# SB2030_Logger_ESP32.net
KiCad netlist of a schematic drawn in EAGLE
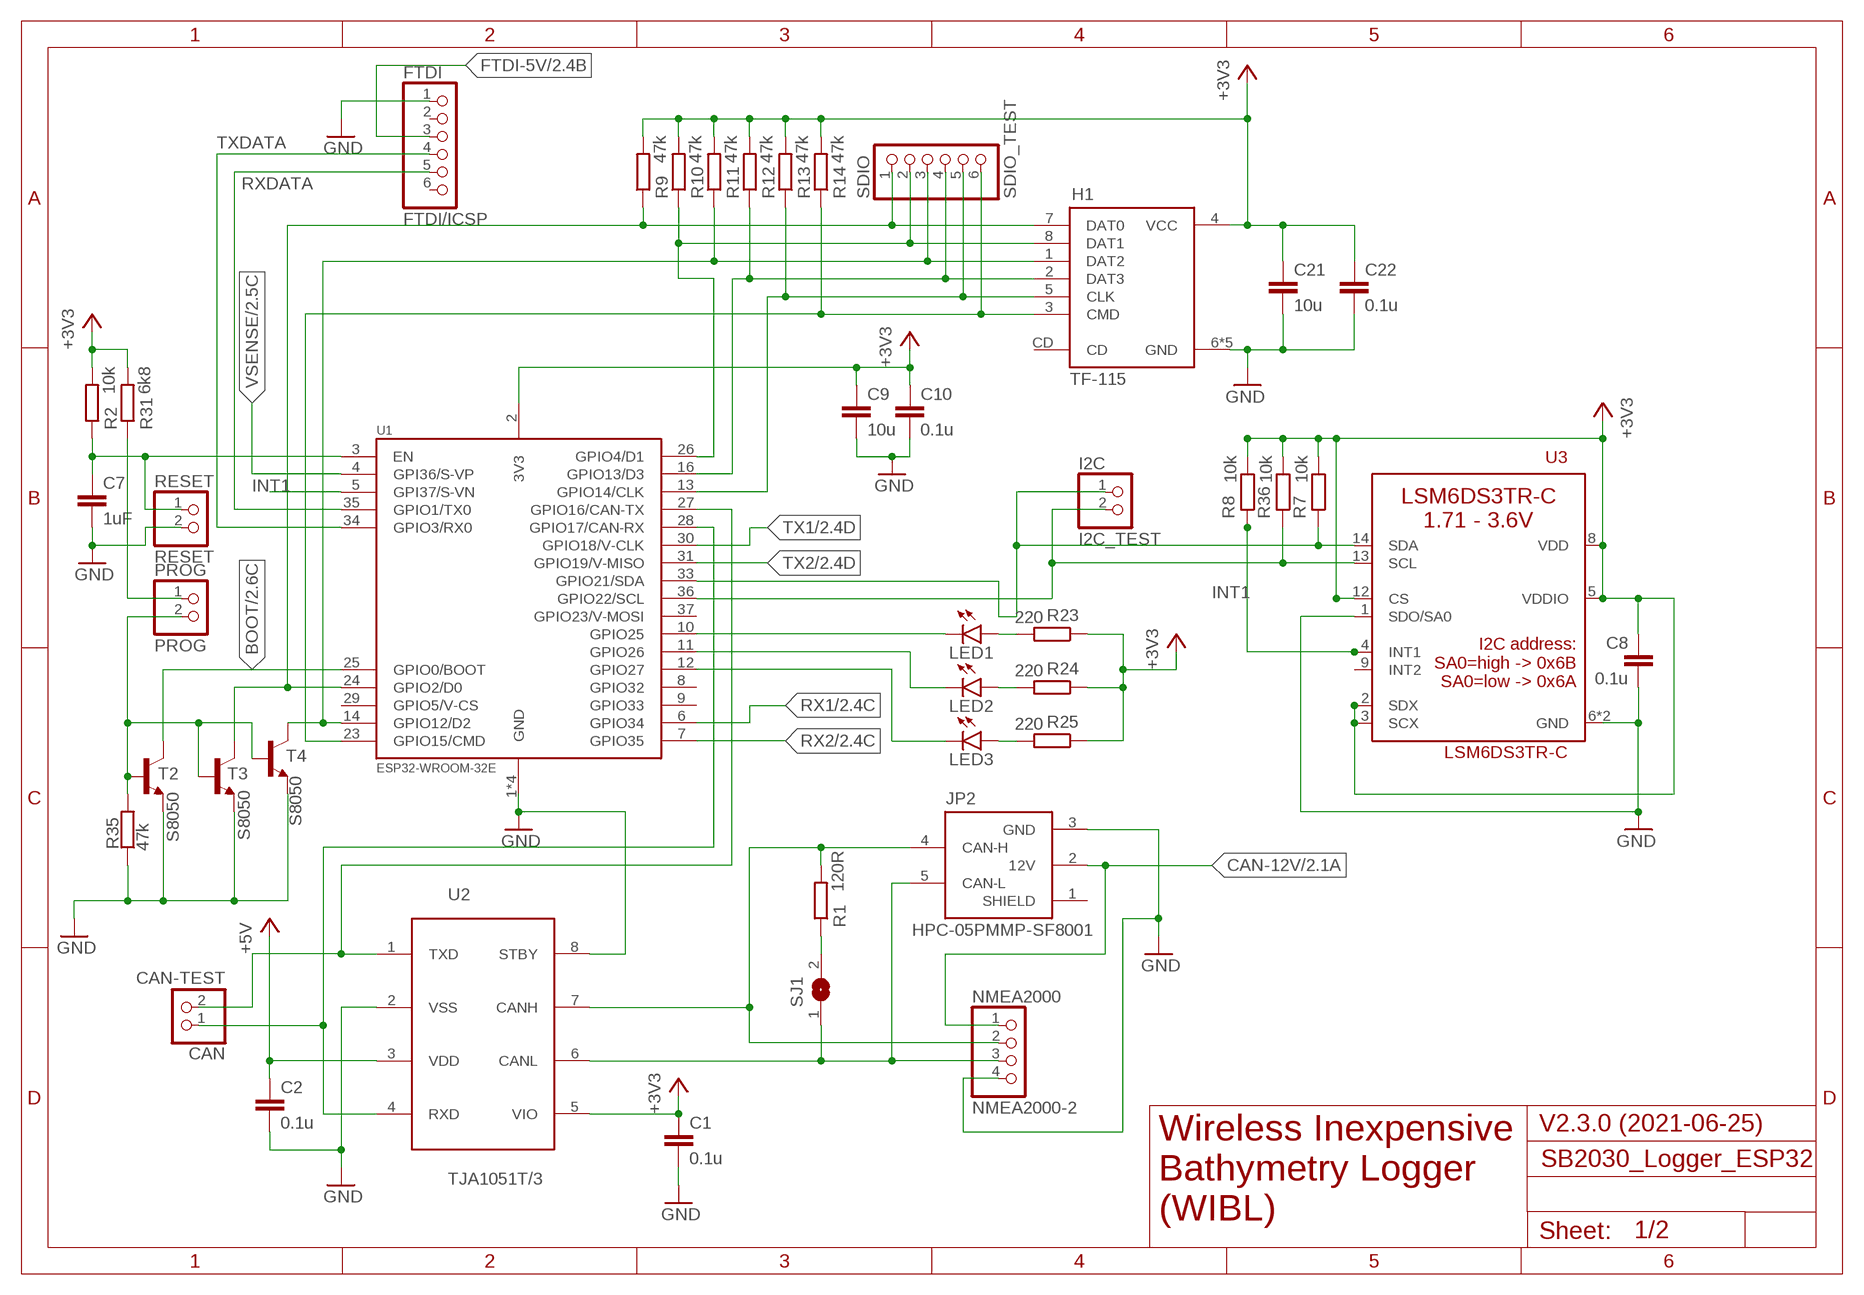
[diagram p0: schematic, sheet 1]
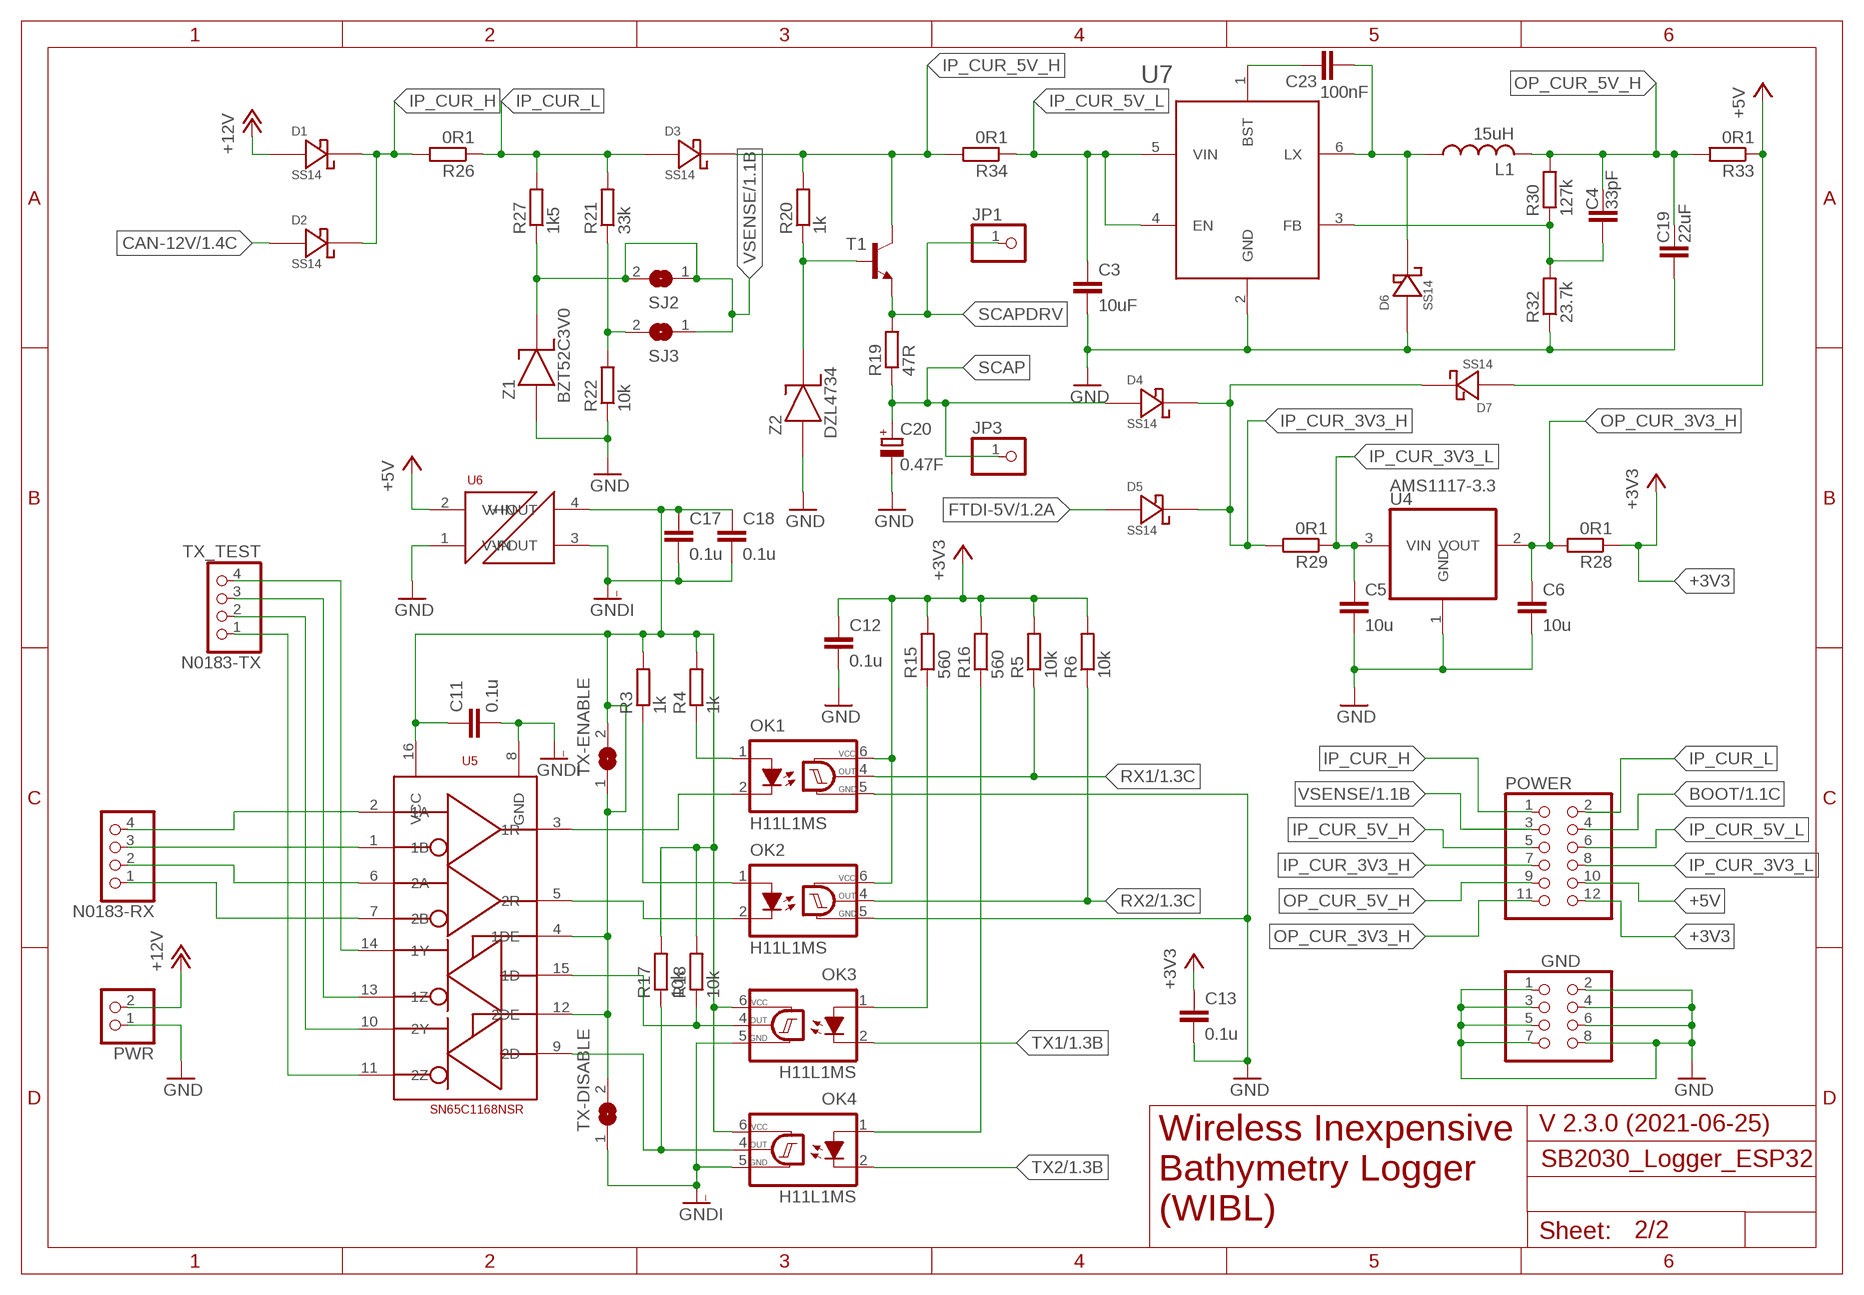
[diagram p1: schematic, sheet 2]

(export (version "E")
  (design (tool "Eeschema 10.0.6"))
  (components
    (comp (ref "C1")
      (value "0.1u")
      (footprint "eagle-import:C0805")
      (libsource (lib "eagle-import") (part "C-EUC0805"))
    )
    (comp (ref "C2")
      (value "0.1u")
      (footprint "eagle-import:C0805")
      (libsource (lib "eagle-import") (part "C-EUC0805"))
    )
    (comp (ref "C7")
      (value "1uF")
      (footprint "eagle-import:C0805")
      (libsource (lib "eagle-import") (part "C-EUC0805"))
    )
    (comp (ref "C8")
      (value "0.1u")
      (footprint "eagle-import:C0805")
      (libsource (lib "eagle-import") (part "C-EUC0805"))
    )
    (comp (ref "C9")
      (value "10u")
      (footprint "eagle-import:C0805")
      (libsource (lib "eagle-import") (part "C-EUC0805"))
    )
    (comp (ref "C10")
      (value "0.1u")
      (footprint "eagle-import:C0805")
      (libsource (lib "eagle-import") (part "C-EUC0805"))
    )
    (comp (ref "C21")
      (value "10u")
      (footprint "eagle-import:C0805")
      (libsource (lib "eagle-import") (part "C-EUC0805"))
    )
    (comp (ref "C22")
      (value "0.1u")
      (footprint "eagle-import:C0805")
      (libsource (lib "eagle-import") (part "C-EUC0805"))
    )
    (comp (ref "CAN")
      (value "CAN-TEST")
      (footprint "eagle-import:1X02")
      (libsource (lib "eagle-import") (part "PINHD-1X2"))
    )
    (comp (ref "FTDI")
      (value "FTDI/ICSP")
      (footprint "eagle-import:1X06")
      (libsource (lib "eagle-import") (part "PINHD-1X6"))
    )
    (comp (ref "H1")
      (value "TF-115")
      (footprint "eagle-import:XUNPU-MICROSD-SOCKET")
      (libsource (lib "eagle-import") (part "XUNPU-MICROSD-SOCKET"))
    )
    (comp (ref "I2C")
      (value "I2C_TEST")
      (footprint "eagle-import:1X02")
      (libsource (lib "eagle-import") (part "PINHD-1X2"))
    )
    (comp (ref "JP2")
      (value "HPC-05PMMP-SF8001")
      (footprint "eagle-import:NMEA2000")
      (libsource (lib "eagle-import") (part "NMEA2000"))
    )
    (comp (ref "LED1")
      (value "LEDCHIP-LED0603")
      (footprint "eagle-import:CHIP-LED0603")
      (libsource (lib "eagle-import") (part "LEDCHIP-LED0603"))
    )
    (comp (ref "LED2")
      (value "LEDCHIP-LED0603")
      (footprint "eagle-import:CHIP-LED0603")
      (libsource (lib "eagle-import") (part "LEDCHIP-LED0603"))
    )
    (comp (ref "LED3")
      (value "LEDCHIP-LED0603")
      (footprint "eagle-import:CHIP-LED0603")
      (libsource (lib "eagle-import") (part "LEDCHIP-LED0603"))
    )
    (comp (ref "NMEA2000")
      (value "NMEA2000-2")
      (footprint "eagle-import:1X04")
      (libsource (lib "eagle-import") (part "PINHD-1X4"))
    )
    (comp (ref "PROG")
      (value "PROG")
      (footprint "eagle-import:1X02")
      (libsource (lib "eagle-import") (part "PINHD-1X2"))
    )
    (comp (ref "R1")
      (value "120R")
      (footprint "eagle-import:R0805")
      (libsource (lib "eagle-import") (part "R-EU_R0805"))
    )
    (comp (ref "R2")
      (value "10k")
      (footprint "eagle-import:R0805")
      (libsource (lib "eagle-import") (part "R-EU_R0805"))
    )
    (comp (ref "R7")
      (value "10k")
      (footprint "eagle-import:R0805")
      (libsource (lib "eagle-import") (part "R-EU_R0805"))
    )
    (comp (ref "R8")
      (value "10k")
      (footprint "eagle-import:R0805")
      (libsource (lib "eagle-import") (part "R-EU_R0805"))
    )
    (comp (ref "R9")
      (value "47k")
      (footprint "eagle-import:R0805")
      (libsource (lib "eagle-import") (part "R-EU_R0805"))
    )
    (comp (ref "R10")
      (value "47k")
      (footprint "eagle-import:R0805")
      (libsource (lib "eagle-import") (part "R-EU_R0805"))
    )
    (comp (ref "R11")
      (value "47k")
      (footprint "eagle-import:R0805")
      (libsource (lib "eagle-import") (part "R-EU_R0805"))
    )
    (comp (ref "R12")
      (value "47k")
      (footprint "eagle-import:R0805")
      (libsource (lib "eagle-import") (part "R-EU_R0805"))
    )
    (comp (ref "R13")
      (value "47k")
      (footprint "eagle-import:R0805")
      (libsource (lib "eagle-import") (part "R-EU_R0805"))
    )
    (comp (ref "R14")
      (value "47k")
      (footprint "eagle-import:R0805")
      (libsource (lib "eagle-import") (part "R-EU_R0805"))
    )
    (comp (ref "R23")
      (value "220")
      (footprint "eagle-import:R0805")
      (libsource (lib "eagle-import") (part "R-EU_R0805"))
    )
    (comp (ref "R24")
      (value "220")
      (footprint "eagle-import:R0805")
      (libsource (lib "eagle-import") (part "R-EU_R0805"))
    )
    (comp (ref "R25")
      (value "220")
      (footprint "eagle-import:R0805")
      (libsource (lib "eagle-import") (part "R-EU_R0805"))
    )
    (comp (ref "R31")
      (value "6k8")
      (footprint "eagle-import:R0805")
      (libsource (lib "eagle-import") (part "R-EU_R0805"))
    )
    (comp (ref "R35")
      (value "47k")
      (footprint "eagle-import:R0805")
      (libsource (lib "eagle-import") (part "R-EU_R0805"))
    )
    (comp (ref "R36")
      (value "10k")
      (footprint "eagle-import:R0805")
      (libsource (lib "eagle-import") (part "R-EU_R0805"))
    )
    (comp (ref "RESET")
      (value "RESET")
      (footprint "eagle-import:1X02")
      (libsource (lib "eagle-import") (part "PINHD-1X2"))
    )
    (comp (ref "SDIO")
      (value "SDIO_TEST")
      (footprint "eagle-import:1X06")
      (libsource (lib "eagle-import") (part "PINHD-1X6"))
    )
    (comp (ref "SJ1") (value "SJ") (footprint "eagle-import:SJ") (libsource (lib "eagle-import") (part "SJ")))
    (comp (ref "T2")
      (value "S8050")
      (footprint "eagle-import:SOT23")
      (libsource (lib "eagle-import") (part "BC846"))
    )
    (comp (ref "T3")
      (value "S8050")
      (footprint "eagle-import:SOT23")
      (libsource (lib "eagle-import") (part "BC846"))
    )
    (comp (ref "T4")
      (value "S8050")
      (footprint "eagle-import:SOT23")
      (libsource (lib "eagle-import") (part "BC846"))
    )
    (comp (ref "U1")
      (value "ESP32-WROOM-32E")
      (footprint "eagle-import:ESPS32-WROOM-32E")
      (libsource (lib "eagle-import") (part "ESP32-WROOM-32E"))
    )
    (comp (ref "U2")
      (value "TJA1051T/3")
      (footprint "eagle-import:SOIC8")
      (libsource (lib "eagle-import") (part "MCP2562T-E/SN"))
    )
    (comp (ref "U3")
      (value "LSM6DS3TR-C")
      (footprint "eagle-import:LGA-14-2.5X3MM")
      (fields (field (name "MF") "STMicroelectronics"))
      (libsource (lib "eagle-import") (part "LSM6DS3TR-C"))
    )
    (comp (ref "C3")
      (value "10uF")
      (footprint "eagle-import:C1206")
      (libsource (lib "eagle-import") (part "C-EUC1206"))
    )
    (comp (ref "C4")
      (value "33pF")
      (footprint "eagle-import:C0603")
      (libsource (lib "eagle-import") (part "C-EUC0603"))
    )
    (comp (ref "C5")
      (value "10u")
      (footprint "eagle-import:C0805")
      (libsource (lib "eagle-import") (part "C-EUC0805"))
    )
    (comp (ref "C6")
      (value "10u")
      (footprint "eagle-import:C0805")
      (libsource (lib "eagle-import") (part "C-EUC0805"))
    )
    (comp (ref "C11")
      (value "0.1u")
      (footprint "eagle-import:C0805")
      (libsource (lib "eagle-import") (part "C-EUC0805"))
    )
    (comp (ref "C12")
      (value "0.1u")
      (footprint "eagle-import:C0805")
      (libsource (lib "eagle-import") (part "C-EUC0805"))
    )
    (comp (ref "C13")
      (value "0.1u")
      (footprint "eagle-import:C0805")
      (libsource (lib "eagle-import") (part "C-EUC0805"))
    )
    (comp (ref "C17")
      (value "0.1u")
      (footprint "eagle-import:C0805")
      (libsource (lib "eagle-import") (part "C-EUC0805"))
    )
    (comp (ref "C18")
      (value "0.1u")
      (footprint "eagle-import:C0805")
      (libsource (lib "eagle-import") (part "C-EUC0805"))
    )
    (comp (ref "C19")
      (value "22uF")
      (footprint "eagle-import:C0603")
      (libsource (lib "eagle-import") (part "C-EUC0603"))
    )
    (comp (ref "C20")
      (value "0.47F")
      (footprint "eagle-import:P128-50")
      (libsource (lib "eagle-import") (part "CPOL-EUP128-50"))
    )
    (comp (ref "C23")
      (value "100nF")
      (footprint "eagle-import:C0402")
      (libsource (lib "eagle-import") (part "C0402"))
    )
    (comp (ref "D1")
      (value "SS14")
      (footprint "eagle-import:DO-214AC")
      (libsource (lib "eagle-import") (part "SS14"))
    )
    (comp (ref "D2")
      (value "SS14")
      (footprint "eagle-import:DO-214AC")
      (libsource (lib "eagle-import") (part "SS14"))
    )
    (comp (ref "D3")
      (value "SS14")
      (footprint "eagle-import:DO-214AC")
      (libsource (lib "eagle-import") (part "SS14"))
    )
    (comp (ref "D4")
      (value "SS14")
      (footprint "eagle-import:DO-214AC")
      (libsource (lib "eagle-import") (part "SS14"))
    )
    (comp (ref "D5")
      (value "SS14")
      (footprint "eagle-import:DO-214AC")
      (libsource (lib "eagle-import") (part "SS14"))
    )
    (comp (ref "D6")
      (value "SS14")
      (footprint "eagle-import:DO-214AC")
      (libsource (lib "eagle-import") (part "SS14"))
    )
    (comp (ref "D7")
      (value "SS14")
      (footprint "eagle-import:DO-214AC")
      (libsource (lib "eagle-import") (part "SS14"))
    )
    (comp (ref "GND")
      (value "PINHD-2X4")
      (footprint "eagle-import:2X04")
      (libsource (lib "eagle-import") (part "PINHD-2X4"))
    )
    (comp (ref "JP1")
      (value "PINHD-1X1")
      (footprint "eagle-import:1X01")
      (libsource (lib "eagle-import") (part "PINHD-1X1"))
    )
    (comp (ref "JP3")
      (value "PINHD-1X1")
      (footprint "eagle-import:1X01")
      (libsource (lib "eagle-import") (part "PINHD-1X1"))
    )
    (comp (ref "L1")
      (value "15uH")
      (footprint "eagle-import:MWSA0603S")
      (libsource (lib "eagle-import") (part "MWSA0603S"))
    )
    (comp (ref "N0183-RX")
      (value "PINHD-1X4")
      (footprint "eagle-import:1X04")
      (libsource (lib "eagle-import") (part "PINHD-1X4"))
    )
    (comp (ref "N0183-TX")
      (value "TX_TEST")
      (footprint "eagle-import:1X04")
      (libsource (lib "eagle-import") (part "PINHD-1X4"))
    )
    (comp (ref "OK1")
      (value "H11L1MS")
      (footprint "eagle-import:DIL6-SMD")
      (libsource (lib "eagle-import") (part "H11LMS1"))
    )
    (comp (ref "OK2")
      (value "H11L1MS")
      (footprint "eagle-import:DIL6-SMD")
      (libsource (lib "eagle-import") (part "H11LMS1"))
    )
    (comp (ref "OK3")
      (value "H11L1MS")
      (footprint "eagle-import:DIL6-SMD")
      (libsource (lib "eagle-import") (part "H11LMS1"))
    )
    (comp (ref "OK4")
      (value "H11L1MS")
      (footprint "eagle-import:DIL6-SMD")
      (libsource (lib "eagle-import") (part "H11LMS1"))
    )
    (comp (ref "POWER")
      (value "PINHD-2X6")
      (footprint "eagle-import:2X06")
      (libsource (lib "eagle-import") (part "PINHD-2X6"))
    )
    (comp (ref "PWR")
      (value "PINHD-1X2")
      (footprint "eagle-import:1X02")
      (libsource (lib "eagle-import") (part "PINHD-1X2"))
    )
    (comp (ref "R3")
      (value "1k")
      (footprint "eagle-import:R0805")
      (libsource (lib "eagle-import") (part "R-EU_R0805"))
    )
    (comp (ref "R4")
      (value "1k")
      (footprint "eagle-import:R0805")
      (libsource (lib "eagle-import") (part "R-EU_R0805"))
    )
    (comp (ref "R5")
      (value "10k")
      (footprint "eagle-import:R0805")
      (libsource (lib "eagle-import") (part "R-EU_R0805"))
    )
    (comp (ref "R6")
      (value "10k")
      (footprint "eagle-import:R0805")
      (libsource (lib "eagle-import") (part "R-EU_R0805"))
    )
    (comp (ref "R15")
      (value "560")
      (footprint "eagle-import:R0805")
      (libsource (lib "eagle-import") (part "R-EU_R0805"))
    )
    (comp (ref "R16")
      (value "560")
      (footprint "eagle-import:R0805")
      (libsource (lib "eagle-import") (part "R-EU_R0805"))
    )
    (comp (ref "R17")
      (value "10k")
      (footprint "eagle-import:R0805")
      (libsource (lib "eagle-import") (part "R-EU_R0805"))
    )
    (comp (ref "R18")
      (value "10k")
      (footprint "eagle-import:R0805")
      (libsource (lib "eagle-import") (part "R-EU_R0805"))
    )
    (comp (ref "R19")
      (value "47R")
      (footprint "eagle-import:R0805")
      (libsource (lib "eagle-import") (part "R-EU_R0805"))
    )
    (comp (ref "R20")
      (value "1k")
      (footprint "eagle-import:R0805")
      (libsource (lib "eagle-import") (part "R-EU_R0805"))
    )
    (comp (ref "R21")
      (value "33k")
      (footprint "eagle-import:R0805")
      (libsource (lib "eagle-import") (part "R-EU_R0805"))
    )
    (comp (ref "R22")
      (value "10k")
      (footprint "eagle-import:R0805")
      (libsource (lib "eagle-import") (part "R-EU_R0805"))
    )
    (comp (ref "R26")
      (value "0R1")
      (footprint "eagle-import:R0603")
      (libsource (lib "eagle-import") (part "R-EU_R0603"))
    )
    (comp (ref "R27")
      (value "1k5")
      (footprint "eagle-import:R0805")
      (libsource (lib "eagle-import") (part "R-EU_R0805"))
    )
    (comp (ref "R28")
      (value "0R1")
      (footprint "eagle-import:R0603")
      (libsource (lib "eagle-import") (part "R-EU_R0603"))
    )
    (comp (ref "R29")
      (value "0R1")
      (footprint "eagle-import:R0603")
      (libsource (lib "eagle-import") (part "R-EU_R0603"))
    )
    (comp (ref "R30")
      (value "127k")
      (footprint "eagle-import:R0603")
      (libsource (lib "eagle-import") (part "R-EU_R0603"))
    )
    (comp (ref "R32")
      (value "23.7k")
      (footprint "eagle-import:R0603")
      (libsource (lib "eagle-import") (part "R-EU_R0603"))
    )
    (comp (ref "R33")
      (value "0R1")
      (footprint "eagle-import:R0603")
      (libsource (lib "eagle-import") (part "R-EU_R0603"))
    )
    (comp (ref "R34")
      (value "0R1")
      (footprint "eagle-import:R0603")
      (libsource (lib "eagle-import") (part "R-EU_R0603"))
    )
    (comp (ref "SJ2") (value "SJ") (footprint "eagle-import:SJ") (libsource (lib "eagle-import") (part "SJ")))
    (comp (ref "SJ3") (value "SJ") (footprint "eagle-import:SJ") (libsource (lib "eagle-import") (part "SJ")))
    (comp (ref "T1")
      (value "BC817-16-NPN-SOT23-BEC")
      (footprint "eagle-import:SOT23-BEC")
      (libsource (lib "eagle-import") (part "-NPN-SOT23-BECBC817-16"))
    )
    (comp (ref "TX-DISABLE")
      (value "SJ")
      (footprint "eagle-import:SJ")
      (libsource (lib "eagle-import") (part "SJ"))
    )
    (comp (ref "TX-ENABLE")
      (value "SJ")
      (footprint "eagle-import:SJ")
      (libsource (lib "eagle-import") (part "SJ"))
    )
    (comp (ref "U4")
      (value "AMS1117-3.3")
      (footprint "eagle-import:SOT223")
      (fields (field (name "MPN") "REG1117"))
      (libsource (lib "eagle-import") (part "REG1117"))
    )
    (comp (ref "U5")
      (value "SN65C1168NSR")
      (footprint "eagle-import:SOIC16")
      (libsource (lib "eagle-import") (part "SN65C1168-SOIC"))
    )
    (comp (ref "U6")
      (value "RFM-0505S")
      (footprint "eagle-import:RFM-0505S")
      (libsource (lib "eagle-import") (part "RFM-0505S"))
    )
    (comp (ref "U7")
      (value "BL9352A")
      (footprint "eagle-import:SOT-23-6L")
      (libsource (lib "eagle-import") (part "BL9352A"))
    )
    (comp (ref "Z1")
      (value "BZT52C3V0")
      (footprint "eagle-import:SOD123")
      (libsource (lib "eagle-import") (part "BZT52C3V0"))
    )
    (comp (ref "Z2")
      (value "DZL4734")
      (footprint "eagle-import:SOD-123FL")
      (libsource (lib "eagle-import") (part "DZL4734"))
    )
  )
  (nets
    (net (code "1") (name "+3V3") (class "Default")
      (node (ref "C1") (pin "1") (pinfunction "1_1") (pintype "passive"))
      (node (ref "C10") (pin "1") (pinfunction "1_1") (pintype "passive"))
      (node (ref "C12") (pin "1") (pinfunction "1_1") (pintype "passive"))
      (node (ref "C13") (pin "1") (pinfunction "1_1") (pintype "passive"))
      (node (ref "C21") (pin "1") (pinfunction "1_1") (pintype "passive"))
      (node (ref "C22") (pin "1") (pinfunction "1_1") (pintype "passive"))
      (node (ref "C8") (pin "1") (pinfunction "1_1") (pintype "passive"))
      (node (ref "C9") (pin "1") (pinfunction "1_1") (pintype "passive"))
      (node (ref "H1") (pin "4") (pinfunction "VCC_4") (pintype "bidirectional"))
      (node (ref "OK1") (pin "6") (pinfunction "VCC_6") (pintype "power_in"))
      (node (ref "OK2") (pin "6") (pinfunction "VCC_6") (pintype "power_in"))
      (node (ref "POWER") (pin "12") (pinfunction "12_12") (pintype "passive"))
      (node (ref "R10") (pin "2") (pinfunction "2_2") (pintype "passive"))
      (node (ref "R11") (pin "2") (pinfunction "2_2") (pintype "passive"))
      (node (ref "R12") (pin "2") (pinfunction "2_2") (pintype "passive"))
      (node (ref "R13") (pin "2") (pinfunction "2_2") (pintype "passive"))
      (node (ref "R14") (pin "2") (pinfunction "2_2") (pintype "passive"))
      (node (ref "R15") (pin "2") (pinfunction "2_2") (pintype "passive"))
      (node (ref "R16") (pin "2") (pinfunction "2_2") (pintype "passive"))
      (node (ref "R2") (pin "2") (pinfunction "2_2") (pintype "passive"))
      (node (ref "R23") (pin "1") (pinfunction "1_1") (pintype "passive"))
      (node (ref "R24") (pin "1") (pinfunction "1_1") (pintype "passive"))
      (node (ref "R25") (pin "1") (pinfunction "1_1") (pintype "passive"))
      (node (ref "R28") (pin "1") (pinfunction "1_1") (pintype "passive"))
      (node (ref "R31") (pin "2") (pinfunction "2_2") (pintype "passive"))
      (node (ref "R36") (pin "2") (pinfunction "2_2") (pintype "passive"))
      (node (ref "R5") (pin "2") (pinfunction "2_2") (pintype "passive"))
      (node (ref "R6") (pin "2") (pinfunction "2_2") (pintype "passive"))
      (node (ref "R7") (pin "2") (pinfunction "2_2") (pintype "passive"))
      (node (ref "R8") (pin "2") (pinfunction "2_2") (pintype "passive"))
      (node (ref "R9") (pin "2") (pinfunction "2_2") (pintype "passive"))
      (node (ref "U1") (pin "2") (pinfunction "3V3_2") (pintype "bidirectional"))
      (node (ref "U2") (pin "5") (pinfunction "VIO_5") (pintype "bidirectional"))
      (node (ref "U3") (pin "12") (pinfunction "CS_12") (pintype "bidirectional"))
      (node (ref "U3") (pin "2") (pinfunction "SDX_2") (pintype "bidirectional"))
      (node (ref "U3") (pin "3") (pinfunction "SCX_3") (pintype "bidirectional"))
      (node (ref "U3") (pin "5") (pinfunction "VDDIO_5") (pintype "bidirectional"))
      (node (ref "U3") (pin "8") (pinfunction "VDD_8") (pintype "bidirectional"))
    )
    (net (code "2") (name "+5V") (class "Default")
      (node (ref "C2") (pin "1") (pinfunction "1_1") (pintype "passive"))
      (node (ref "D7") (pin "A") (pinfunction "A_A") (pintype "bidirectional"))
      (node (ref "POWER") (pin "10") (pinfunction "10_10") (pintype "passive"))
      (node (ref "R33") (pin "1") (pinfunction "1_1") (pintype "passive"))
      (node (ref "U2") (pin "3") (pinfunction "VDD_3") (pintype "bidirectional"))
      (node (ref "U6") (pin "2") (pinfunction "V+IN_2") (pintype "bidirectional"))
    )
    (net (code "3") (name "+12V") (class "Default")
      (node (ref "D1") (pin "A") (pinfunction "A_A") (pintype "bidirectional"))
      (node (ref "PWR") (pin "2") (pinfunction "2_2") (pintype "passive"))
    )
    (net (code "4") (name "BOOT") (class "Default")
      (node (ref "POWER") (pin "4") (pinfunction "4_4") (pintype "passive"))
      (node (ref "T2") (pin "3") (pinfunction "C_3") (pintype "passive"))
      (node (ref "U1") (pin "25") (pinfunction "GPIO0/BOOT_25") (pintype "bidirectional"))
    )
    (net (code "5") (name "CAN-12V") (class "Default")
      (node (ref "D2") (pin "A") (pinfunction "A_A") (pintype "bidirectional"))
      (node (ref "JP2") (pin "2") (pinfunction "12V_2") (pintype "bidirectional"))
      (node (ref "NMEA2000") (pin "1") (pinfunction "1_1") (pintype "passive"))
    )
    (net (code "6") (name "FTDI-5V") (class "Default")
      (node (ref "D5") (pin "A") (pinfunction "A_A") (pintype "bidirectional"))
      (node (ref "FTDI") (pin "3") (pinfunction "3_3") (pintype "passive"))
    )
    (net (code "7") (name "GND") (class "Default")
      (node (ref "C1") (pin "2") (pinfunction "2_2") (pintype "passive"))
      (node (ref "C10") (pin "2") (pinfunction "2_2") (pintype "passive"))
      (node (ref "C12") (pin "2") (pinfunction "2_2") (pintype "passive"))
      (node (ref "C13") (pin "2") (pinfunction "2_2") (pintype "passive"))
      (node (ref "C19") (pin "1") (pinfunction "1_1") (pintype "passive"))
      (node (ref "C2") (pin "2") (pinfunction "2_2") (pintype "passive"))
      (node (ref "C20") (pin "-") (pinfunction "-_-") (pintype "passive"))
      (node (ref "C21") (pin "2") (pinfunction "2_2") (pintype "passive"))
      (node (ref "C22") (pin "2") (pinfunction "2_2") (pintype "passive"))
      (node (ref "C3") (pin "2") (pinfunction "2_2") (pintype "passive"))
      (node (ref "C5") (pin "2") (pinfunction "2_2") (pintype "passive"))
      (node (ref "C6") (pin "2") (pinfunction "2_2") (pintype "passive"))
      (node (ref "C7") (pin "2") (pinfunction "2_2") (pintype "passive"))
      (node (ref "C8") (pin "2") (pinfunction "2_2") (pintype "passive"))
      (node (ref "C9") (pin "2") (pinfunction "2_2") (pintype "passive"))
      (node (ref "D6") (pin "A") (pinfunction "A_A") (pintype "bidirectional"))
      (node (ref "FTDI") (pin "1") (pinfunction "1_1") (pintype "passive"))
      (node (ref "GND") (pin "1") (pinfunction "1_1") (pintype "passive"))
      (node (ref "GND") (pin "2") (pinfunction "2_2") (pintype "passive"))
      (node (ref "GND") (pin "3") (pinfunction "3_3") (pintype "passive"))
      (node (ref "GND") (pin "4") (pinfunction "4_4") (pintype "passive"))
      (node (ref "GND") (pin "5") (pinfunction "5_5") (pintype "passive"))
      (node (ref "GND") (pin "6") (pinfunction "6_6") (pintype "passive"))
      (node (ref "GND") (pin "7") (pinfunction "7_7") (pintype "passive"))
      (node (ref "GND") (pin "8") (pinfunction "8_8") (pintype "passive"))
      (node (ref "H1") (pin "6") (pinfunction "GND_6") (pintype "bidirectional"))
      (node (ref "H1") (pin "GND1") (pinfunction "GND_GND1") (pintype "bidirectional"))
      (node (ref "H1") (pin "GND2") (pinfunction "GND_GND2") (pintype "bidirectional"))
      (node (ref "H1") (pin "GND3") (pinfunction "GND_GND3") (pintype "bidirectional"))
      (node (ref "H1") (pin "GND4") (pinfunction "GND_GND4") (pintype "bidirectional"))
      (node (ref "JP2") (pin "3") (pinfunction "GND_3") (pintype "bidirectional"))
      (node (ref "NMEA2000") (pin "4") (pinfunction "4_4") (pintype "passive"))
      (node (ref "OK1") (pin "5") (pinfunction "GND_5") (pintype "power_in"))
      (node (ref "OK2") (pin "5") (pinfunction "GND_5") (pintype "power_in"))
      (node (ref "PWR") (pin "1") (pinfunction "1_1") (pintype "passive"))
      (node (ref "R22") (pin "1") (pinfunction "1_1") (pintype "passive"))
      (node (ref "R32") (pin "1") (pinfunction "1_1") (pintype "passive"))
      (node (ref "R35") (pin "1") (pinfunction "1_1") (pintype "passive"))
      (node (ref "RESET") (pin "2") (pinfunction "2_2") (pintype "passive"))
      (node (ref "T2") (pin "2") (pinfunction "E_2") (pintype "passive"))
      (node (ref "T3") (pin "2") (pinfunction "E_2") (pintype "passive"))
      (node (ref "T4") (pin "2") (pinfunction "E_2") (pintype "passive"))
      (node (ref "U1") (pin "1") (pinfunction "GND_1") (pintype "bidirectional"))
      (node (ref "U1") (pin "15") (pinfunction "GND_15") (pintype "bidirectional"))
      (node (ref "U1") (pin "38") (pinfunction "GND_38") (pintype "bidirectional"))
      (node (ref "U1") (pin "THERM") (pinfunction "GND_THERM") (pintype "bidirectional"))
      (node (ref "U2") (pin "2") (pinfunction "VSS_2") (pintype "bidirectional"))
      (node (ref "U2") (pin "8") (pinfunction "STBY_8") (pintype "bidirectional"))
      (node (ref "U3") (pin "1") (pinfunction "SDO/SA0_1") (pintype "bidirectional"))
      (node (ref "U3") (pin "6") (pinfunction "GND_6") (pintype "bidirectional"))
      (node (ref "U3") (pin "7") (pinfunction "GND_7") (pintype "bidirectional"))
      (node (ref "U4") (pin "1") (pinfunction "GND_1") (pintype "power_in"))
      (node (ref "U6") (pin "1") (pinfunction "V-IN_1") (pintype "bidirectional"))
      (node (ref "U7") (pin "2") (pinfunction "GND_2") (pintype "bidirectional"))
      (node (ref "Z1") (pin "1") (pinfunction "A_1") (pintype "bidirectional"))
      (node (ref "Z2") (pin "A") (pinfunction "A_A") (pintype "bidirectional"))
    )
    (net (code "8") (name "GNDI") (class "Default")
      (node (ref "C11") (pin "2") (pinfunction "2_2") (pintype "passive"))
      (node (ref "C17") (pin "2") (pinfunction "2_2") (pintype "passive"))
      (node (ref "C18") (pin "2") (pinfunction "2_2") (pintype "passive"))
      (node (ref "OK3") (pin "5") (pinfunction "GND_5") (pintype "power_in"))
      (node (ref "OK4") (pin "5") (pinfunction "GND_5") (pintype "power_in"))
      (node (ref "TX-DISABLE") (pin "1") (pinfunction "1_1") (pintype "passive"))
      (node (ref "U5") (pin "8") (pinfunction "GND_8") (pintype "bidirectional"))
      (node (ref "U6") (pin "3") (pinfunction "V-OUT_3") (pintype "bidirectional"))
    )
    (net (code "9") (name "INT1") (class "Default")
      (node (ref "R8") (pin "1") (pinfunction "1_1") (pintype "passive"))
      (node (ref "U1") (pin "5") (pinfunction "GPI37/S-VN_5") (pintype "bidirectional"))
      (node (ref "U3") (pin "4") (pinfunction "INT1_4") (pintype "bidirectional"))
    )
    (net (code "10") (name "IP_CUR_3V3_H") (class "Default")
      (node (ref "D4") (pin "K") (pinfunction "K_K") (pintype "bidirectional"))
      (node (ref "D5") (pin "K") (pinfunction "K_K") (pintype "bidirectional"))
      (node (ref "D7") (pin "K") (pinfunction "K_K") (pintype "bidirectional"))
      (node (ref "POWER") (pin "7") (pinfunction "7_7") (pintype "passive"))
      (node (ref "R29") (pin "2") (pinfunction "2_2") (pintype "passive"))
    )
    (net (code "11") (name "IP_CUR_3V3_L") (class "Default")
      (node (ref "C5") (pin "1") (pinfunction "1_1") (pintype "passive"))
      (node (ref "POWER") (pin "8") (pinfunction "8_8") (pintype "passive"))
      (node (ref "R29") (pin "1") (pinfunction "1_1") (pintype "passive"))
      (node (ref "U4") (pin "3") (pinfunction "VIN_3") (pintype "input"))
    )
    (net (code "12") (name "IP_CUR_5V_H") (class "Default")
      (node (ref "D3") (pin "K") (pinfunction "K_K") (pintype "bidirectional"))
      (node (ref "POWER") (pin "5") (pinfunction "5_5") (pintype "passive"))
      (node (ref "R20") (pin "2") (pinfunction "2_2") (pintype "passive"))
      (node (ref "R34") (pin "2") (pinfunction "2_2") (pintype "passive"))
      (node (ref "T1") (pin "C") (pinfunction "C_C") (pintype "passive"))
    )
    (net (code "13") (name "IP_CUR_5V_L") (class "Default")
      (node (ref "C3") (pin "1") (pinfunction "1_1") (pintype "passive"))
      (node (ref "POWER") (pin "6") (pinfunction "6_6") (pintype "passive"))
      (node (ref "R34") (pin "1") (pinfunction "1_1") (pintype "passive"))
      (node (ref "U7") (pin "4") (pinfunction "EN_4") (pintype "bidirectional"))
      (node (ref "U7") (pin "5") (pinfunction "VIN_5") (pintype "bidirectional"))
    )
    (net (code "14") (name "IP_CUR_H") (class "Default")
      (node (ref "D1") (pin "K") (pinfunction "K_K") (pintype "bidirectional"))
      (node (ref "D2") (pin "K") (pinfunction "K_K") (pintype "bidirectional"))
      (node (ref "POWER") (pin "1") (pinfunction "1_1") (pintype "passive"))
      (node (ref "R26") (pin "2") (pinfunction "2_2") (pintype "passive"))
    )
    (net (code "15") (name "IP_CUR_L") (class "Default")
      (node (ref "D3") (pin "A") (pinfunction "A_A") (pintype "bidirectional"))
      (node (ref "POWER") (pin "2") (pinfunction "2_2") (pintype "passive"))
      (node (ref "R21") (pin "2") (pinfunction "2_2") (pintype "passive"))
      (node (ref "R26") (pin "1") (pinfunction "1_1") (pintype "passive"))
      (node (ref "R27") (pin "2") (pinfunction "2_2") (pintype "passive"))
    )
    (net (code "16") (name "Net-(C23-1)") (class "Default")
      (node (ref "C23") (pin "P$1") (pinfunction "1_P$1") (pintype "passive"))
      (node (ref "U7") (pin "1") (pinfunction "BST_1") (pintype "bidirectional"))
    )
    (net (code "17") (name "Net-(C23-2)") (class "Default")
      (node (ref "C23") (pin "P$2") (pinfunction "2_P$2") (pintype "passive"))
      (node (ref "D6") (pin "K") (pinfunction "K_K") (pintype "bidirectional"))
      (node (ref "L1") (pin "P$1") (pinfunction "1_P$1") (pintype "passive"))
      (node (ref "U7") (pin "6") (pinfunction "LX_6") (pintype "bidirectional"))
    )
    (net (code "18") (name "Net-(H1-CLK)") (class "Default")
      (node (ref "H1") (pin "5") (pinfunction "CLK_5") (pintype "bidirectional"))
      (node (ref "R13") (pin "1") (pinfunction "1_1") (pintype "passive"))
      (node (ref "SDIO") (pin "5") (pinfunction "5_5") (pintype "passive"))
      (node (ref "U1") (pin "13") (pinfunction "GPIO14/CLK_13") (pintype "bidirectional"))
    )
    (net (code "19") (name "Net-(H1-CMD)") (class "Default")
      (node (ref "H1") (pin "3") (pinfunction "CMD_3") (pintype "bidirectional"))
      (node (ref "R14") (pin "1") (pinfunction "1_1") (pintype "passive"))
      (node (ref "SDIO") (pin "6") (pinfunction "6_6") (pintype "passive"))
      (node (ref "U1") (pin "23") (pinfunction "GPIO15/CMD_23") (pintype "bidirectional"))
    )
    (net (code "20") (name "Net-(H1-DAT0)") (class "Default")
      (node (ref "H1") (pin "7") (pinfunction "DAT0_7") (pintype "bidirectional"))
      (node (ref "R9") (pin "1") (pinfunction "1_1") (pintype "passive"))
      (node (ref "SDIO") (pin "1") (pinfunction "1_1") (pintype "passive"))
      (node (ref "T3") (pin "3") (pinfunction "C_3") (pintype "passive"))
      (node (ref "U1") (pin "24") (pinfunction "GPIO2/D0_24") (pintype "bidirectional"))
    )
    (net (code "21") (name "Net-(H1-DAT1)") (class "Default")
      (node (ref "H1") (pin "8") (pinfunction "DAT1_8") (pintype "bidirectional"))
      (node (ref "R10") (pin "1") (pinfunction "1_1") (pintype "passive"))
      (node (ref "SDIO") (pin "2") (pinfunction "2_2") (pintype "passive"))
      (node (ref "U1") (pin "26") (pinfunction "GPIO4/D1_26") (pintype "bidirectional"))
    )
    (net (code "22") (name "Net-(H1-DAT2)") (class "Default")
      (node (ref "H1") (pin "1") (pinfunction "DAT2_1") (pintype "bidirectional"))
      (node (ref "R11") (pin "1") (pinfunction "1_1") (pintype "passive"))
      (node (ref "SDIO") (pin "3") (pinfunction "3_3") (pintype "passive"))
      (node (ref "T4") (pin "3") (pinfunction "C_3") (pintype "passive"))
      (node (ref "U1") (pin "14") (pinfunction "GPIO12/D2_14") (pintype "bidirectional"))
    )
    (net (code "23") (name "Net-(H1-DAT3)") (class "Default")
      (node (ref "H1") (pin "2") (pinfunction "DAT3_2") (pintype "bidirectional"))
      (node (ref "R12") (pin "1") (pinfunction "1_1") (pintype "passive"))
      (node (ref "SDIO") (pin "4") (pinfunction "4_4") (pintype "passive"))
      (node (ref "U1") (pin "16") (pinfunction "GPIO13/D3_16") (pintype "bidirectional"))
    )
    (net (code "24") (name "Net-(JP2-CAN-H)") (class "Default")
      (node (ref "JP2") (pin "4") (pinfunction "CAN-H_4") (pintype "bidirectional"))
      (node (ref "NMEA2000") (pin "2") (pinfunction "2_2") (pintype "passive"))
      (node (ref "R1") (pin "2") (pinfunction "2_2") (pintype "passive"))
      (node (ref "U2") (pin "7") (pinfunction "CANH_7") (pintype "bidirectional"))
    )
    (net (code "25") (name "Net-(JP2-CAN-L)") (class "Default")
      (node (ref "JP2") (pin "5") (pinfunction "CAN-L_5") (pintype "bidirectional"))
      (node (ref "NMEA2000") (pin "3") (pinfunction "3_3") (pintype "passive"))
      (node (ref "SJ1") (pin "1") (pinfunction "1_1") (pintype "passive"))
      (node (ref "U2") (pin "6") (pinfunction "CANL_6") (pintype "bidirectional"))
    )
    (net (code "26") (name "Net-(LED1-PadA)") (class "Default")
      (node (ref "LED1") (pin "A") (pinfunction "A_A") (pintype "passive"))
      (node (ref "R23") (pin "2") (pinfunction "2_2") (pintype "passive"))
    )
    (net (code "27") (name "Net-(LED2-PadA)") (class "Default")
      (node (ref "LED2") (pin "A") (pinfunction "A_A") (pintype "passive"))
      (node (ref "R24") (pin "2") (pinfunction "2_2") (pintype "passive"))
    )
    (net (code "28") (name "Net-(LED3-PadA)") (class "Default")
      (node (ref "LED3") (pin "A") (pinfunction "A_A") (pintype "passive"))
      (node (ref "R25") (pin "2") (pinfunction "2_2") (pintype "passive"))
    )
    (net (code "29") (name "Net-(OK1-A)") (class "Default")
      (node (ref "OK1") (pin "1") (pinfunction "A_1") (pintype "passive"))
      (node (ref "R4") (pin "1") (pinfunction "1_1") (pintype "passive"))
    )
    (net (code "30") (name "Net-(OK1-C)") (class "Default")
      (node (ref "OK1") (pin "2") (pinfunction "C_2") (pintype "passive"))
      (node (ref "U5") (pin "3") (pinfunction "1R_3") (pintype "bidirectional"))
    )
    (net (code "31") (name "Net-(OK2-A)") (class "Default")
      (node (ref "OK2") (pin "1") (pinfunction "A_1") (pintype "passive"))
      (node (ref "R3") (pin "1") (pinfunction "1_1") (pintype "passive"))
    )
    (net (code "32") (name "Net-(OK2-C)") (class "Default")
      (node (ref "OK2") (pin "2") (pinfunction "C_2") (pintype "passive"))
      (node (ref "U5") (pin "5") (pinfunction "2R_5") (pintype "bidirectional"))
    )
    (net (code "33") (name "Net-(OK3-A)") (class "Default")
      (node (ref "OK3") (pin "1") (pinfunction "A_1") (pintype "passive"))
      (node (ref "R15") (pin "1") (pinfunction "1_1") (pintype "passive"))
    )
    (net (code "34") (name "Net-(OK3-OUT)") (class "Default")
      (node (ref "OK3") (pin "4") (pinfunction "OUT_4") (pintype "output"))
      (node (ref "R18") (pin "1") (pinfunction "1_1") (pintype "passive"))
      (node (ref "U5") (pin "15") (pinfunction "1D_15") (pintype "bidirectional"))
    )
    (net (code "35") (name "Net-(OK3-VCC)") (class "Default")
      (node (ref "C11") (pin "1") (pinfunction "1_1") (pintype "passive"))
      (node (ref "C17") (pin "1") (pinfunction "1_1") (pintype "passive"))
      (node (ref "C18") (pin "1") (pinfunction "1_1") (pintype "passive"))
      (node (ref "OK3") (pin "6") (pinfunction "VCC_6") (pintype "power_in"))
      (node (ref "OK4") (pin "6") (pinfunction "VCC_6") (pintype "power_in"))
      (node (ref "R17") (pin "2") (pinfunction "2_2") (pintype "passive"))
      (node (ref "R18") (pin "2") (pinfunction "2_2") (pintype "passive"))
      (node (ref "R3") (pin "2") (pinfunction "2_2") (pintype "passive"))
      (node (ref "R4") (pin "2") (pinfunction "2_2") (pintype "passive"))
      (node (ref "TX-DISABLE") (pin "2") (pinfunction "2_2") (pintype "passive"))
      (node (ref "TX-ENABLE") (pin "1") (pinfunction "1_1") (pintype "passive"))
      (node (ref "TX-ENABLE") (pin "2") (pinfunction "2_2") (pintype "passive"))
      (node (ref "U5") (pin "12") (pinfunction "2DE_12") (pintype "bidirectional"))
      (node (ref "U5") (pin "16") (pinfunction "VCC_16") (pintype "bidirectional"))
      (node (ref "U5") (pin "4") (pinfunction "1DE_4") (pintype "bidirectional"))
      (node (ref "U6") (pin "4") (pinfunction "V+OUT_4") (pintype "bidirectional"))
    )
    (net (code "36") (name "Net-(OK4-A)") (class "Default")
      (node (ref "OK4") (pin "1") (pinfunction "A_1") (pintype "passive"))
      (node (ref "R16") (pin "1") (pinfunction "1_1") (pintype "passive"))
    )
    (net (code "37") (name "Net-(OK4-OUT)") (class "Default")
      (node (ref "OK4") (pin "4") (pinfunction "OUT_4") (pintype "output"))
      (node (ref "R17") (pin "1") (pinfunction "1_1") (pintype "passive"))
      (node (ref "U5") (pin "9") (pinfunction "2D_9") (pintype "bidirectional"))
    )
    (net (code "38") (name "Net-(PROG-Pad1)") (class "Default")
      (node (ref "PROG") (pin "1") (pinfunction "1_1") (pintype "passive"))
      (node (ref "R31") (pin "1") (pinfunction "1_1") (pintype "passive"))
    )
    (net (code "39") (name "Net-(R1-Pad1)") (class "Default")
      (node (ref "R1") (pin "1") (pinfunction "1_1") (pintype "passive"))
      (node (ref "SJ1") (pin "2") (pinfunction "2_2") (pintype "passive"))
    )
    (net (code "40") (name "Net-(R20-Pad1)") (class "Default")
      (node (ref "R20") (pin "1") (pinfunction "1_1") (pintype "passive"))
      (node (ref "T1") (pin "B") (pinfunction "B_B") (pintype "passive"))
      (node (ref "Z2") (pin "K") (pinfunction "K_K") (pintype "bidirectional"))
    )
    (net (code "41") (name "Net-(R21-Pad1)") (class "Default")
      (node (ref "R21") (pin "1") (pinfunction "1_1") (pintype "passive"))
      (node (ref "R22") (pin "2") (pinfunction "2_2") (pintype "passive"))
      (node (ref "SJ3") (pin "2") (pinfunction "2_2") (pintype "passive"))
    )
    (net (code "42") (name "Net-(T2-B)") (class "Default")
      (node (ref "PROG") (pin "2") (pinfunction "2_2") (pintype "passive"))
      (node (ref "R35") (pin "2") (pinfunction "2_2") (pintype "passive"))
      (node (ref "T2") (pin "1") (pinfunction "B_1") (pintype "passive"))
      (node (ref "T3") (pin "1") (pinfunction "B_1") (pintype "passive"))
      (node (ref "T4") (pin "1") (pinfunction "B_1") (pintype "passive"))
    )
    (net (code "43") (name "Net-(U1-EN)") (class "Default")
      (node (ref "C7") (pin "1") (pinfunction "1_1") (pintype "passive"))
      (node (ref "R2") (pin "1") (pinfunction "1_1") (pintype "passive"))
      (node (ref "RESET") (pin "1") (pinfunction "1_1") (pintype "passive"))
      (node (ref "U1") (pin "3") (pinfunction "EN_3") (pintype "bidirectional"))
    )
    (net (code "44") (name "Net-(U1-GPIO16{slash}CAN-TX)") (class "Default")
      (node (ref "CAN") (pin "2") (pinfunction "2_2") (pintype "passive"))
      (node (ref "U1") (pin "27") (pinfunction "GPIO16/CAN-TX_27") (pintype "bidirectional"))
      (node (ref "U2") (pin "1") (pinfunction "TXD_1") (pintype "bidirectional"))
    )
    (net (code "45") (name "Net-(U1-GPIO17{slash}CAN-RX)") (class "Default")
      (node (ref "CAN") (pin "1") (pinfunction "1_1") (pintype "passive"))
      (node (ref "U1") (pin "28") (pinfunction "GPIO17/CAN-RX_28") (pintype "bidirectional"))
      (node (ref "U2") (pin "4") (pinfunction "RXD_4") (pintype "bidirectional"))
    )
    (net (code "46") (name "Net-(U1-GPIO21{slash}SDA)") (class "Default")
      (node (ref "I2C") (pin "1") (pinfunction "1_1") (pintype "passive"))
      (node (ref "R7") (pin "1") (pinfunction "1_1") (pintype "passive"))
      (node (ref "U1") (pin "33") (pinfunction "GPIO21/SDA_33") (pintype "bidirectional"))
      (node (ref "U3") (pin "14") (pinfunction "SDA_14") (pintype "bidirectional"))
    )
    (net (code "47") (name "Net-(U1-GPIO22{slash}SCL)") (class "Default")
      (node (ref "I2C") (pin "2") (pinfunction "2_2") (pintype "passive"))
      (node (ref "R36") (pin "1") (pinfunction "1_1") (pintype "passive"))
      (node (ref "U1") (pin "36") (pinfunction "GPIO22/SCL_36") (pintype "bidirectional"))
      (node (ref "U3") (pin "13") (pinfunction "SCL_13") (pintype "bidirectional"))
    )
    (net (code "48") (name "Net-(U1-GPIO25)") (class "Default")
      (node (ref "LED1") (pin "C") (pinfunction "C_C") (pintype "passive"))
      (node (ref "U1") (pin "10") (pinfunction "GPIO25_10") (pintype "bidirectional"))
    )
    (net (code "49") (name "Net-(U1-GPIO26)") (class "Default")
      (node (ref "LED2") (pin "C") (pinfunction "C_C") (pintype "passive"))
      (node (ref "U1") (pin "11") (pinfunction "GPIO26_11") (pintype "bidirectional"))
    )
    (net (code "50") (name "Net-(U1-GPIO27)") (class "Default")
      (node (ref "LED3") (pin "C") (pinfunction "C_C") (pintype "passive"))
      (node (ref "U1") (pin "12") (pinfunction "GPIO27_12") (pintype "bidirectional"))
    )
    (net (code "51") (name "Net-(U5-1A)") (class "Default")
      (node (ref "N0183-RX") (pin "4") (pinfunction "4_4") (pintype "passive"))
      (node (ref "U5") (pin "2") (pinfunction "1A_2") (pintype "bidirectional"))
    )
    (net (code "52") (name "Net-(U5-1B)") (class "Default")
      (node (ref "N0183-RX") (pin "3") (pinfunction "3_3") (pintype "passive"))
      (node (ref "U5") (pin "1") (pinfunction "1B_1") (pintype "bidirectional"))
    )
    (net (code "53") (name "Net-(U5-1Y)") (class "Default")
      (node (ref "N0183-TX") (pin "4") (pinfunction "4_4") (pintype "passive"))
      (node (ref "U5") (pin "14") (pinfunction "1Y_14") (pintype "bidirectional"))
    )
    (net (code "54") (name "Net-(U5-1Z)") (class "Default")
      (node (ref "N0183-TX") (pin "3") (pinfunction "3_3") (pintype "passive"))
      (node (ref "U5") (pin "13") (pinfunction "1Z_13") (pintype "bidirectional"))
    )
    (net (code "55") (name "Net-(U5-2A)") (class "Default")
      (node (ref "N0183-RX") (pin "2") (pinfunction "2_2") (pintype "passive"))
      (node (ref "U5") (pin "6") (pinfunction "2A_6") (pintype "bidirectional"))
    )
    (net (code "56") (name "Net-(U5-2B)") (class "Default")
      (node (ref "N0183-RX") (pin "1") (pinfunction "1_1") (pintype "passive"))
      (node (ref "U5") (pin "7") (pinfunction "2B_7") (pintype "bidirectional"))
    )
    (net (code "57") (name "Net-(U5-2Y)") (class "Default")
      (node (ref "N0183-TX") (pin "2") (pinfunction "2_2") (pintype "passive"))
      (node (ref "U5") (pin "10") (pinfunction "2Y_10") (pintype "bidirectional"))
    )
    (net (code "58") (name "Net-(U5-2Z)") (class "Default")
      (node (ref "N0183-TX") (pin "1") (pinfunction "1_1") (pintype "passive"))
      (node (ref "U5") (pin "11") (pinfunction "2Z_11") (pintype "bidirectional"))
    )
    (net (code "59") (name "Net-(U7-FB)") (class "Default")
      (node (ref "C4") (pin "1") (pinfunction "1_1") (pintype "passive"))
      (node (ref "R30") (pin "1") (pinfunction "1_1") (pintype "passive"))
      (node (ref "R32") (pin "2") (pinfunction "2_2") (pintype "passive"))
      (node (ref "U7") (pin "3") (pinfunction "FB_3") (pintype "bidirectional"))
    )
    (net (code "60") (name "OP_CUR_3V3_H") (class "Default")
      (node (ref "C6") (pin "1") (pinfunction "1_1") (pintype "passive"))
      (node (ref "POWER") (pin "11") (pinfunction "11_11") (pintype "passive"))
      (node (ref "R28") (pin "2") (pinfunction "2_2") (pintype "passive"))
      (node (ref "U4") (pin "2") (pinfunction "VOUT_2") (pintype "output"))
    )
    (net (code "61") (name "OP_CUR_5V_H") (class "Default")
      (node (ref "C19") (pin "2") (pinfunction "2_2") (pintype "passive"))
      (node (ref "C4") (pin "2") (pinfunction "2_2") (pintype "passive"))
      (node (ref "L1") (pin "P$2") (pinfunction "2_P$2") (pintype "passive"))
      (node (ref "POWER") (pin "9") (pinfunction "9_9") (pintype "passive"))
      (node (ref "R30") (pin "2") (pinfunction "2_2") (pintype "passive"))
      (node (ref "R33") (pin "2") (pinfunction "2_2") (pintype "passive"))
    )
    (net (code "62") (name "RX1") (class "Default")
      (node (ref "OK1") (pin "4") (pinfunction "OUT_4") (pintype "output"))
      (node (ref "R5") (pin "1") (pinfunction "1_1") (pintype "passive"))
      (node (ref "U1") (pin "6") (pinfunction "GPIO34_6") (pintype "bidirectional"))
    )
    (net (code "63") (name "RX2") (class "Default")
      (node (ref "OK2") (pin "4") (pinfunction "OUT_4") (pintype "output"))
      (node (ref "R6") (pin "1") (pinfunction "1_1") (pintype "passive"))
      (node (ref "U1") (pin "7") (pinfunction "GPIO35_7") (pintype "bidirectional"))
    )
    (net (code "64") (name "RXDATA") (class "Default")
      (node (ref "FTDI") (pin "5") (pinfunction "5_5") (pintype "passive"))
      (node (ref "U1") (pin "35") (pinfunction "GPIO1/TX0_35") (pintype "bidirectional"))
    )
    (net (code "65") (name "SCAP") (class "Default")
      (node (ref "C20") (pin "+") (pinfunction "+_+") (pintype "passive"))
      (node (ref "D4") (pin "A") (pinfunction "A_A") (pintype "bidirectional"))
      (node (ref "JP3") (pin "1") (pinfunction "1_1") (pintype "passive"))
      (node (ref "R19") (pin "1") (pinfunction "1_1") (pintype "passive"))
    )
    (net (code "66") (name "SCAPDRV") (class "Default")
      (node (ref "JP1") (pin "1") (pinfunction "1_1") (pintype "passive"))
      (node (ref "R19") (pin "2") (pinfunction "2_2") (pintype "passive"))
      (node (ref "T1") (pin "E") (pinfunction "E_E") (pintype "passive"))
    )
    (net (code "67") (name "TX1") (class "Default")
      (node (ref "OK3") (pin "2") (pinfunction "C_2") (pintype "passive"))
      (node (ref "U1") (pin "30") (pinfunction "GPIO18/V-CLK_30") (pintype "bidirectional"))
    )
    (net (code "68") (name "TX2") (class "Default")
      (node (ref "OK4") (pin "2") (pinfunction "C_2") (pintype "passive"))
      (node (ref "U1") (pin "31") (pinfunction "GPIO19/V-MISO_31") (pintype "bidirectional"))
    )
    (net (code "69") (name "TXDATA") (class "Default")
      (node (ref "FTDI") (pin "4") (pinfunction "4_4") (pintype "passive"))
      (node (ref "U1") (pin "34") (pinfunction "GPIO3/RX0_34") (pintype "bidirectional"))
    )
    (net (code "70") (name "VSENSE") (class "Default")
      (node (ref "POWER") (pin "3") (pinfunction "3_3") (pintype "passive"))
      (node (ref "R27") (pin "1") (pinfunction "1_1") (pintype "passive"))
      (node (ref "SJ2") (pin "1") (pinfunction "1_1") (pintype "passive"))
      (node (ref "SJ2") (pin "2") (pinfunction "2_2") (pintype "passive"))
      (node (ref "SJ3") (pin "1") (pinfunction "1_1") (pintype "passive"))
      (node (ref "U1") (pin "4") (pinfunction "GPI36/S-VP_4") (pintype "bidirectional"))
      (node (ref "Z1") (pin "2") (pinfunction "K_2") (pintype "bidirectional"))
    )
    (net (code "71") (name "unconnected-(FTDI-Pad2)") (class "Default")
      (node (ref "FTDI") (pin "2") (pinfunction "2_2") (pintype "passive"))
    )
    (net (code "72") (name "unconnected-(FTDI-Pad6)") (class "Default")
      (node (ref "FTDI") (pin "6") (pinfunction "6_6") (pintype "passive"))
    )
    (net (code "73") (name "unconnected-(H1-PadCD)") (class "Default")
      (node (ref "H1") (pin "CD") (pinfunction "CD_CD") (pintype "bidirectional"))
    )
    (net (code "74") (name "unconnected-(JP2-SHIELD-Pad1)") (class "Default")
      (node (ref "JP2") (pin "1") (pinfunction "SHIELD_1") (pintype "bidirectional"))
    )
    (net (code "75") (name "unconnected-(U1-GPIO5{slash}V-CS-Pad29)") (class "Default")
      (node (ref "U1") (pin "29") (pinfunction "GPIO5/V-CS_29") (pintype "bidirectional"))
    )
    (net (code "76") (name "unconnected-(U1-GPIO23{slash}V-MOSI-Pad37)") (class "Default")
      (node (ref "U1") (pin "37") (pinfunction "GPIO23/V-MOSI_37") (pintype "bidirectional"))
    )
    (net (code "77") (name "unconnected-(U1-GPIO32-Pad8)") (class "Default")
      (node (ref "U1") (pin "8") (pinfunction "GPIO32_8") (pintype "bidirectional"))
    )
    (net (code "78") (name "unconnected-(U1-GPIO33-Pad9)") (class "Default")
      (node (ref "U1") (pin "9") (pinfunction "GPIO33_9") (pintype "bidirectional"))
    )
    (net (code "79") (name "unconnected-(U3-INT2-Pad9)") (class "Default")
      (node (ref "U3") (pin "9") (pinfunction "INT2_9") (pintype "bidirectional"))
    )
  )
)
